# SCH_Satlla_4_rpi_board_2023-01-29.net
KiCad netlist of a schematic drawn in EasyEDA
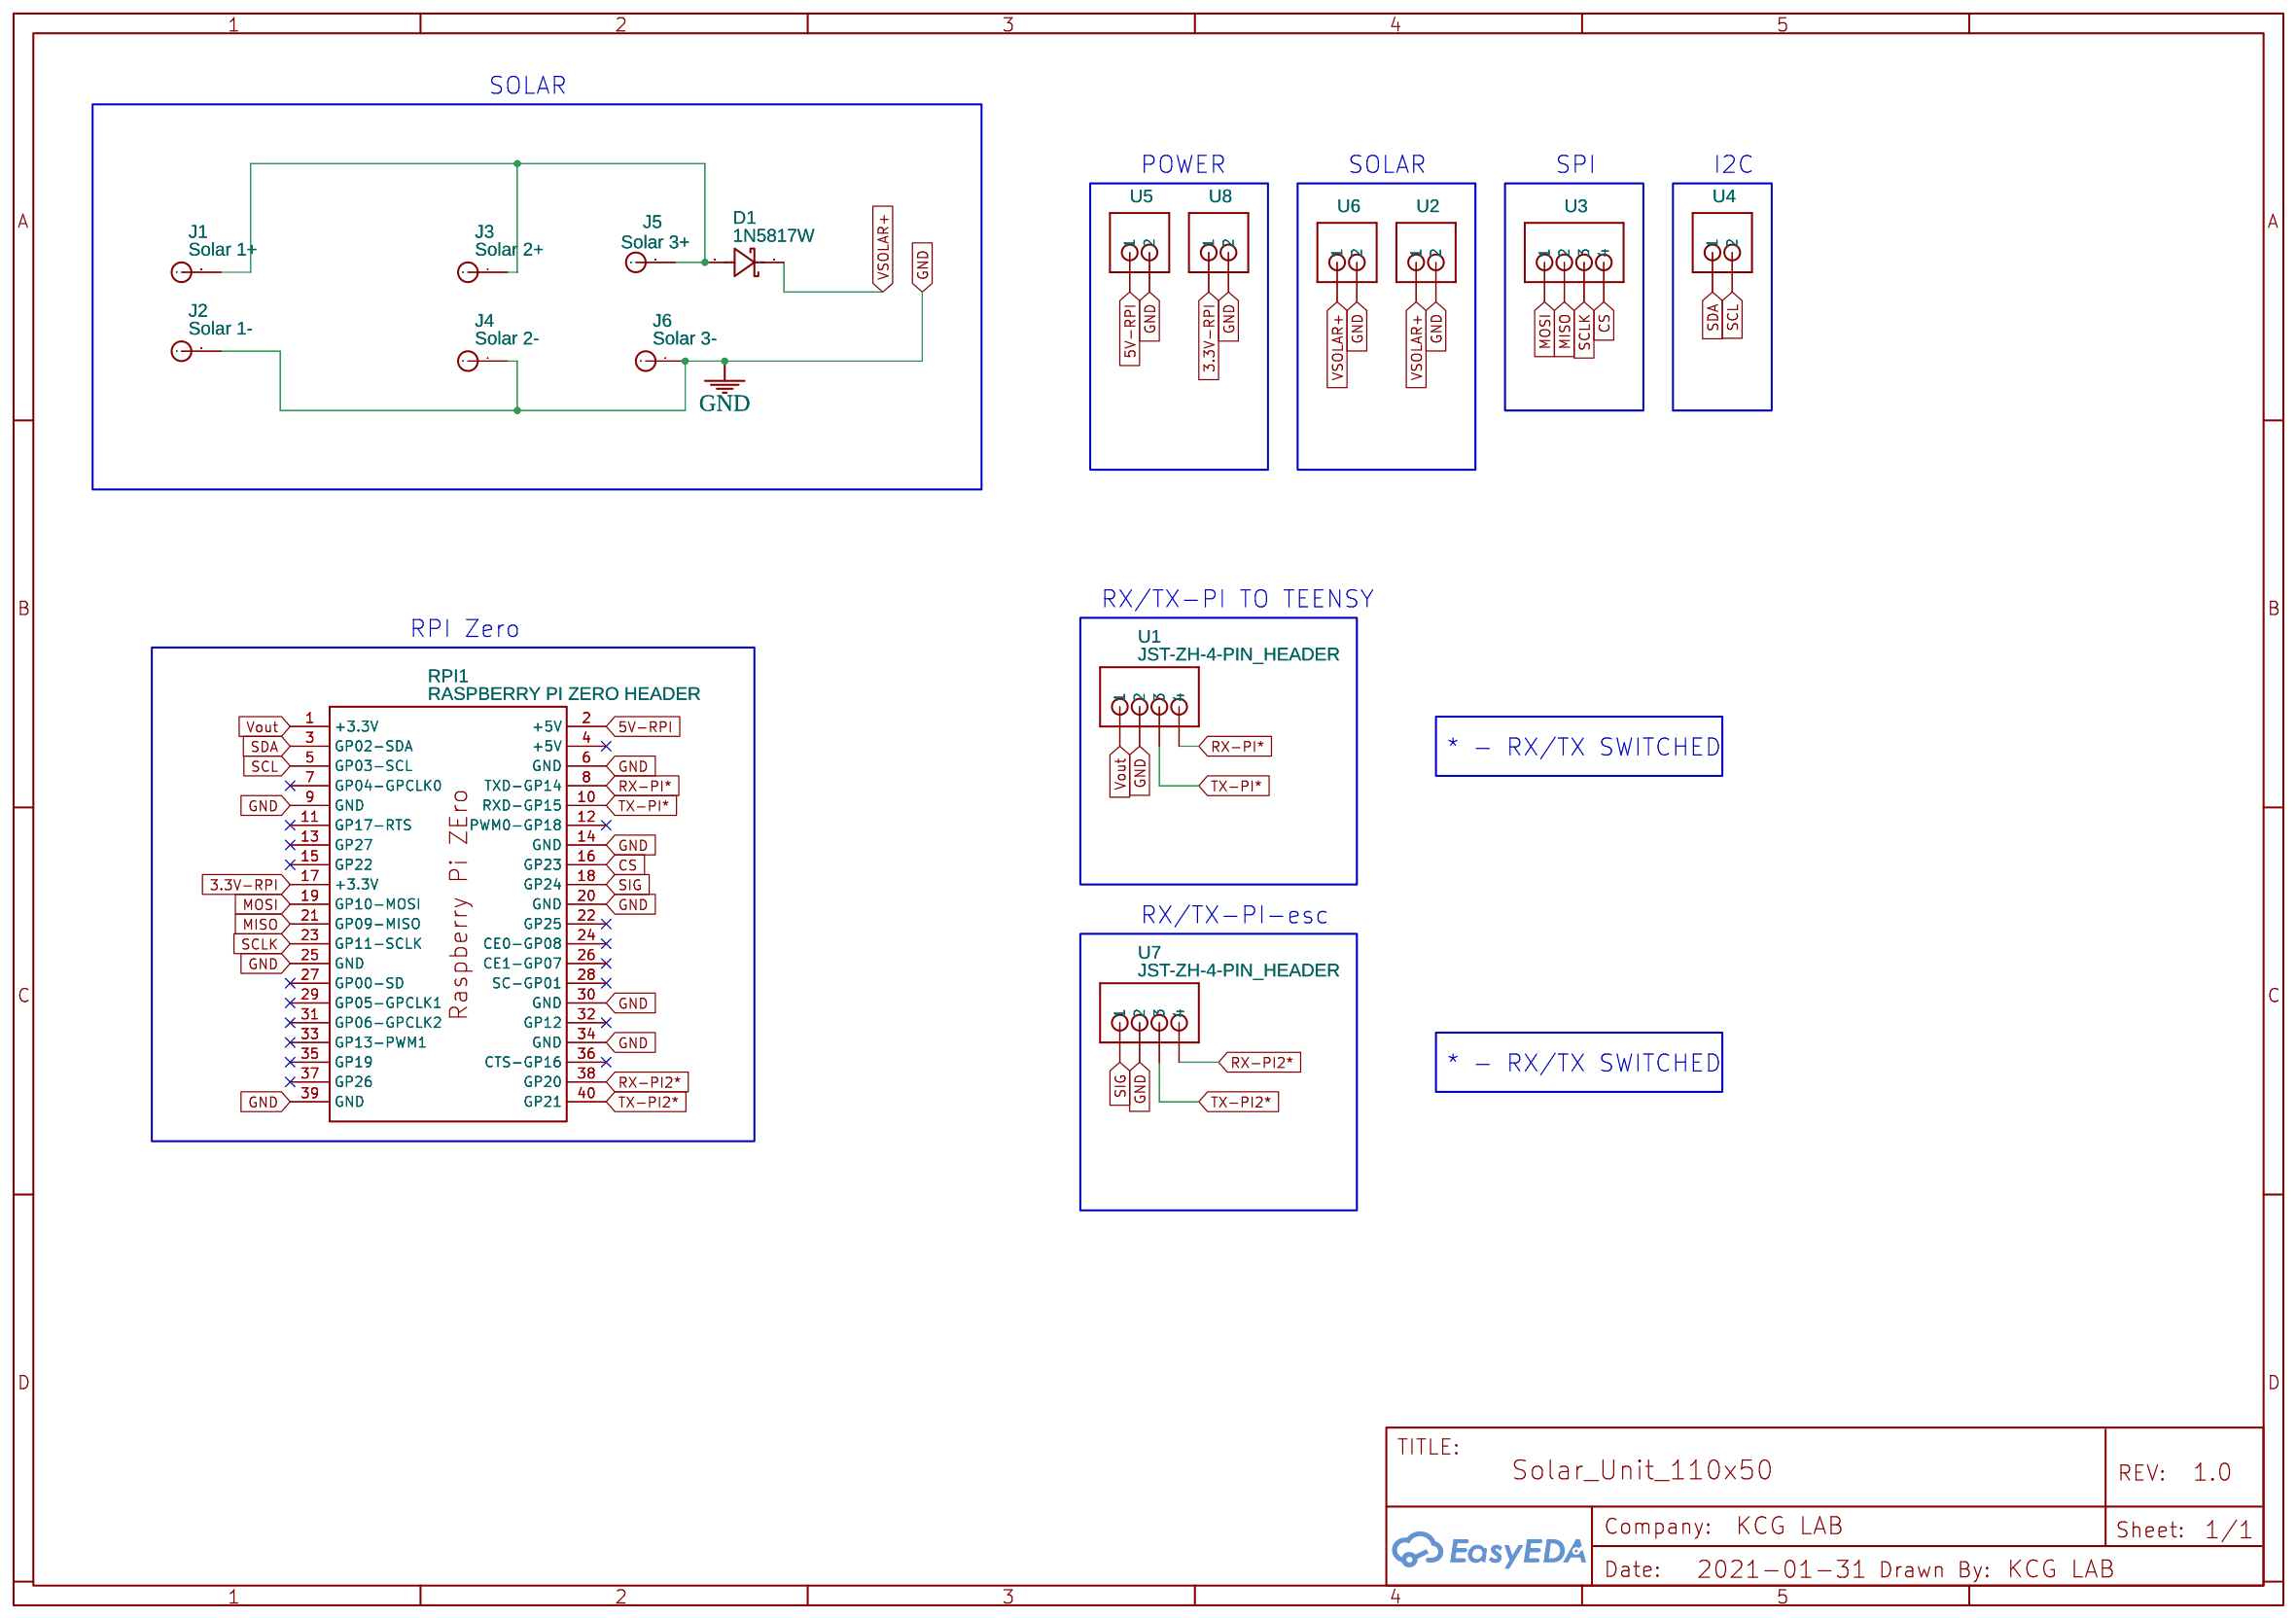
[diagram p0: schematic sheet]

(export (version "E")
  (design (tool "Eeschema 10.0.6"))
  (components
    (comp (ref "D1")
      (value "1N5817W")
      (fields (field (name "BOM_Supplier Part") "C727113"))
      (libsource (lib "") (part "1N5817W"))
    )
    (comp (ref "J1")
      (value "Solar 1+")
      (fields
        (field (name "BOM_Manufacturer Part") "RF130-1013BBS0741")
        (field (name "BOM_Supplier Part") "320030026")
      )
      (libsource (lib "") (part "Connector"))
    )
    (comp (ref "J2")
      (value "Solar 1-")
      (fields
        (field (name "BOM_Manufacturer Part") "RF130-1013BBS0741")
        (field (name "BOM_Supplier Part") "320030026")
      )
      (libsource (lib "") (part "Connector"))
    )
    (comp (ref "J3")
      (value "Solar 2+")
      (fields
        (field (name "BOM_Manufacturer Part") "RF130-1013BBS0741")
        (field (name "BOM_Supplier Part") "320030026")
      )
      (libsource (lib "") (part "Connector"))
    )
    (comp (ref "J4")
      (value "Solar 2-")
      (fields
        (field (name "BOM_Manufacturer Part") "RF130-1013BBS0741")
        (field (name "BOM_Supplier Part") "320030026")
      )
      (libsource (lib "") (part "Connector"))
    )
    (comp (ref "J5")
      (value "Solar 3+")
      (fields
        (field (name "BOM_Manufacturer Part") "RF130-1013BBS0741")
        (field (name "BOM_Supplier Part") "320030026")
      )
      (libsource (lib "") (part "Connector"))
    )
    (comp (ref "J6")
      (value "Solar 3-")
      (fields
        (field (name "BOM_Manufacturer Part") "RF130-1013BBS0741")
        (field (name "BOM_Supplier Part") "320030026")
      )
      (libsource (lib "") (part "Connector"))
    )
    (comp (ref "RPI1")
      (value "RASPBERRY PI ZERO HEADER")
      (fields
        (field (name "BOM_Manufacturer Part") "Raspberry Pi Zero WH")
        (field (name "BOM_Supplier Part") "810885")
      )
      (libsource (lib "") (part "RASPBERRY PI ZERO HEADER"))
    )
    (comp (ref "U1") (value "JST-ZH-4-PIN_HEADER") (libsource (lib "") (part "JST-ZH-4-PIN_HEADER")))
    (comp (ref "U2") (value "JST-ZH-2-PIN_HEADER TH") (libsource (lib "") (part "JST-ZH-2-PIN_HEADER TH")))
    (comp (ref "U3") (value "JST-ZH-4-PIN_HEADER") (libsource (lib "") (part "JST-ZH-4-PIN_HEADER")))
    (comp (ref "U4") (value "JST-ZH-2-PIN_HEADER TH") (libsource (lib "") (part "JST-ZH-2-PIN_HEADER TH")))
    (comp (ref "U5") (value "JST-ZH-2-PIN_HEADER TH") (libsource (lib "") (part "JST-ZH-2-PIN_HEADER TH")))
    (comp (ref "U6") (value "JST-ZH-2-PIN_HEADER TH") (libsource (lib "") (part "JST-ZH-2-PIN_HEADER TH")))
    (comp (ref "U7") (value "JST-ZH-4-PIN_HEADER") (libsource (lib "") (part "JST-ZH-4-PIN_HEADER")))
    (comp (ref "U8") (value "JST-ZH-2-PIN_HEADER TH") (libsource (lib "") (part "JST-ZH-2-PIN_HEADER TH")))
  )
  (nets
    (net (code "1") (name "3.3V-RPI") (class "Default")
      (node (ref "RPI1") (pin "17") (pinfunction "+3.3V_17") (pintype "unspecified"))
      (node (ref "U8") (pin "1") (pinfunction "1_1") (pintype "unspecified"))
    )
    (net (code "2") (name "5V-RPI") (class "Default")
      (node (ref "RPI1") (pin "2") (pinfunction "+5V_2") (pintype "unspecified"))
      (node (ref "U5") (pin "1") (pinfunction "1_1") (pintype "unspecified"))
    )
    (net (code "3") (name "CS") (class "Default")
      (node (ref "RPI1") (pin "16") (pinfunction "GP23_16") (pintype "unspecified"))
      (node (ref "U3") (pin "P4") (pinfunction "4_P4") (pintype "unspecified"))
    )
    (net (code "4") (name "GND") (class "Default")
      (node (ref "J2") (pin "1") (pinfunction "1_1") (pintype "unspecified"))
      (node (ref "J4") (pin "1") (pinfunction "1_1") (pintype "unspecified"))
      (node (ref "J6") (pin "1") (pinfunction "1_1") (pintype "unspecified"))
      (node (ref "RPI1") (pin "14") (pinfunction "GND_14") (pintype "unspecified"))
      (node (ref "RPI1") (pin "20") (pinfunction "GND_20") (pintype "unspecified"))
      (node (ref "RPI1") (pin "25") (pinfunction "GND_25") (pintype "unspecified"))
      (node (ref "RPI1") (pin "30") (pinfunction "GND_30") (pintype "unspecified"))
      (node (ref "RPI1") (pin "34") (pinfunction "GND_34") (pintype "unspecified"))
      (node (ref "RPI1") (pin "39") (pinfunction "GND_39") (pintype "unspecified"))
      (node (ref "RPI1") (pin "6") (pinfunction "GND_6") (pintype "unspecified"))
      (node (ref "RPI1") (pin "9") (pinfunction "GND_9") (pintype "unspecified"))
      (node (ref "U1") (pin "P2") (pinfunction "2_P2") (pintype "unspecified"))
      (node (ref "U2") (pin "2") (pinfunction "2_2") (pintype "unspecified"))
      (node (ref "U5") (pin "2") (pinfunction "2_2") (pintype "unspecified"))
      (node (ref "U6") (pin "2") (pinfunction "2_2") (pintype "unspecified"))
      (node (ref "U7") (pin "P2") (pinfunction "2_P2") (pintype "unspecified"))
      (node (ref "U8") (pin "2") (pinfunction "2_2") (pintype "unspecified"))
    )
    (net (code "5") (name "MISO") (class "Default")
      (node (ref "RPI1") (pin "21") (pinfunction "GP09-MISO_21") (pintype "unspecified"))
      (node (ref "U3") (pin "P2") (pinfunction "2_P2") (pintype "unspecified"))
    )
    (net (code "6") (name "MOSI") (class "Default")
      (node (ref "RPI1") (pin "19") (pinfunction "GP10-MOSI_19") (pintype "unspecified"))
      (node (ref "U3") (pin "P1") (pinfunction "1_P1") (pintype "unspecified"))
    )
    (net (code "7") (name "Net-(D1-A)") (class "Default")
      (node (ref "D1") (pin "2") (pinfunction "A_2") (pintype "unspecified"))
      (node (ref "J1") (pin "1") (pinfunction "1_1") (pintype "unspecified"))
      (node (ref "J3") (pin "1") (pinfunction "1_1") (pintype "unspecified"))
      (node (ref "J5") (pin "1") (pinfunction "1_1") (pintype "unspecified"))
    )
    (net (code "8") (name "RX-PI*") (class "Default")
      (node (ref "RPI1") (pin "8") (pinfunction "TXD-GP14_8") (pintype "unspecified"))
      (node (ref "U1") (pin "P4") (pinfunction "4_P4") (pintype "unspecified"))
    )
    (net (code "9") (name "RX-PI2*") (class "Default")
      (node (ref "RPI1") (pin "38") (pinfunction "GP20_38") (pintype "unspecified"))
      (node (ref "U7") (pin "P4") (pinfunction "4_P4") (pintype "unspecified"))
    )
    (net (code "10") (name "SCL") (class "Default")
      (node (ref "RPI1") (pin "5") (pinfunction "GP03-SCL_5") (pintype "unspecified"))
      (node (ref "U4") (pin "2") (pinfunction "2_2") (pintype "unspecified"))
    )
    (net (code "11") (name "SCLK") (class "Default")
      (node (ref "RPI1") (pin "23") (pinfunction "GP11-SCLK_23") (pintype "unspecified"))
      (node (ref "U3") (pin "P3") (pinfunction "3_P3") (pintype "unspecified"))
    )
    (net (code "12") (name "SDA") (class "Default")
      (node (ref "RPI1") (pin "3") (pinfunction "GP02-SDA_3") (pintype "unspecified"))
      (node (ref "U4") (pin "1") (pinfunction "1_1") (pintype "unspecified"))
    )
    (net (code "13") (name "SIG") (class "Default")
      (node (ref "RPI1") (pin "18") (pinfunction "GP24_18") (pintype "unspecified"))
      (node (ref "U7") (pin "P1") (pinfunction "1_P1") (pintype "unspecified"))
    )
    (net (code "14") (name "TX-PI*") (class "Default")
      (node (ref "RPI1") (pin "10") (pinfunction "RXD-GP15_10") (pintype "unspecified"))
      (node (ref "U1") (pin "P3") (pinfunction "3_P3") (pintype "unspecified"))
    )
    (net (code "15") (name "TX-PI2*") (class "Default")
      (node (ref "RPI1") (pin "40") (pinfunction "GP21_40") (pintype "unspecified"))
      (node (ref "U7") (pin "P3") (pinfunction "3_P3") (pintype "unspecified"))
    )
    (net (code "16") (name "VSOLAR+") (class "Default")
      (node (ref "D1") (pin "1") (pinfunction "C_1") (pintype "unspecified"))
      (node (ref "U2") (pin "1") (pinfunction "1_1") (pintype "unspecified"))
      (node (ref "U6") (pin "1") (pinfunction "1_1") (pintype "unspecified"))
    )
    (net (code "17") (name "Vout") (class "Default")
      (node (ref "RPI1") (pin "1") (pinfunction "+3.3V_1") (pintype "unspecified"))
      (node (ref "U1") (pin "P1") (pinfunction "1_P1") (pintype "unspecified"))
    )
    (net (code "18") (name "unconnected-(RPI1-+5V-Pad4)") (class "Default")
      (node (ref "RPI1") (pin "4") (pinfunction "+5V_4") (pintype "unspecified+no_connect"))
    )
    (net (code "19") (name "unconnected-(RPI1-CE0-GP08-Pad24)") (class "Default")
      (node (ref "RPI1") (pin "24") (pinfunction "CE0-GP08_24") (pintype "unspecified+no_connect"))
    )
    (net (code "20") (name "unconnected-(RPI1-CE1-GP07-Pad26)") (class "Default")
      (node (ref "RPI1") (pin "26") (pinfunction "CE1-GP07_26") (pintype "unspecified+no_connect"))
    )
    (net (code "21") (name "unconnected-(RPI1-CTS-GP16-Pad36)") (class "Default")
      (node (ref "RPI1") (pin "36") (pinfunction "CTS-GP16_36") (pintype "unspecified+no_connect"))
    )
    (net (code "22") (name "unconnected-(RPI1-GP00-SD-Pad27)") (class "Default")
      (node (ref "RPI1") (pin "27") (pinfunction "GP00-SD_27") (pintype "unspecified+no_connect"))
    )
    (net (code "23") (name "unconnected-(RPI1-GP04-GPCLK0-Pad7)") (class "Default")
      (node (ref "RPI1") (pin "7") (pinfunction "GP04-GPCLK0_7") (pintype "unspecified+no_connect"))
    )
    (net (code "24") (name "unconnected-(RPI1-GP05-GPCLK1-Pad29)") (class "Default")
      (node (ref "RPI1") (pin "29") (pinfunction "GP05-GPCLK1_29") (pintype "unspecified+no_connect"))
    )
    (net (code "25") (name "unconnected-(RPI1-GP06-GPCLK2-Pad31)") (class "Default")
      (node (ref "RPI1") (pin "31") (pinfunction "GP06-GPCLK2_31") (pintype "unspecified+no_connect"))
    )
    (net (code "26") (name "unconnected-(RPI1-GP12-Pad32)") (class "Default")
      (node (ref "RPI1") (pin "32") (pinfunction "GP12_32") (pintype "unspecified+no_connect"))
    )
    (net (code "27") (name "unconnected-(RPI1-GP13-PWM1-Pad33)") (class "Default")
      (node (ref "RPI1") (pin "33") (pinfunction "GP13-PWM1_33") (pintype "unspecified+no_connect"))
    )
    (net (code "28") (name "unconnected-(RPI1-GP17-RTS-Pad11)") (class "Default")
      (node (ref "RPI1") (pin "11") (pinfunction "GP17-RTS_11") (pintype "unspecified+no_connect"))
    )
    (net (code "29") (name "unconnected-(RPI1-GP19-Pad35)") (class "Default")
      (node (ref "RPI1") (pin "35") (pinfunction "GP19_35") (pintype "unspecified+no_connect"))
    )
    (net (code "30") (name "unconnected-(RPI1-GP22-Pad15)") (class "Default")
      (node (ref "RPI1") (pin "15") (pinfunction "GP22_15") (pintype "unspecified+no_connect"))
    )
    (net (code "31") (name "unconnected-(RPI1-GP25-Pad22)") (class "Default")
      (node (ref "RPI1") (pin "22") (pinfunction "GP25_22") (pintype "unspecified+no_connect"))
    )
    (net (code "32") (name "unconnected-(RPI1-GP26-Pad37)") (class "Default")
      (node (ref "RPI1") (pin "37") (pinfunction "GP26_37") (pintype "unspecified+no_connect"))
    )
    (net (code "33") (name "unconnected-(RPI1-GP27-Pad13)") (class "Default")
      (node (ref "RPI1") (pin "13") (pinfunction "GP27_13") (pintype "unspecified+no_connect"))
    )
    (net (code "34") (name "unconnected-(RPI1-PWM0-GP18-Pad12)") (class "Default")
      (node (ref "RPI1") (pin "12") (pinfunction "PWM0-GP18_12") (pintype "unspecified+no_connect"))
    )
    (net (code "35") (name "unconnected-(RPI1-SC-GP01-Pad28)") (class "Default")
      (node (ref "RPI1") (pin "28") (pinfunction "SC-GP01_28") (pintype "unspecified+no_connect"))
    )
  )
)
